# X7A15T-Decoupling.net
KiCad netlist of a schematic drawn in Altium Designer
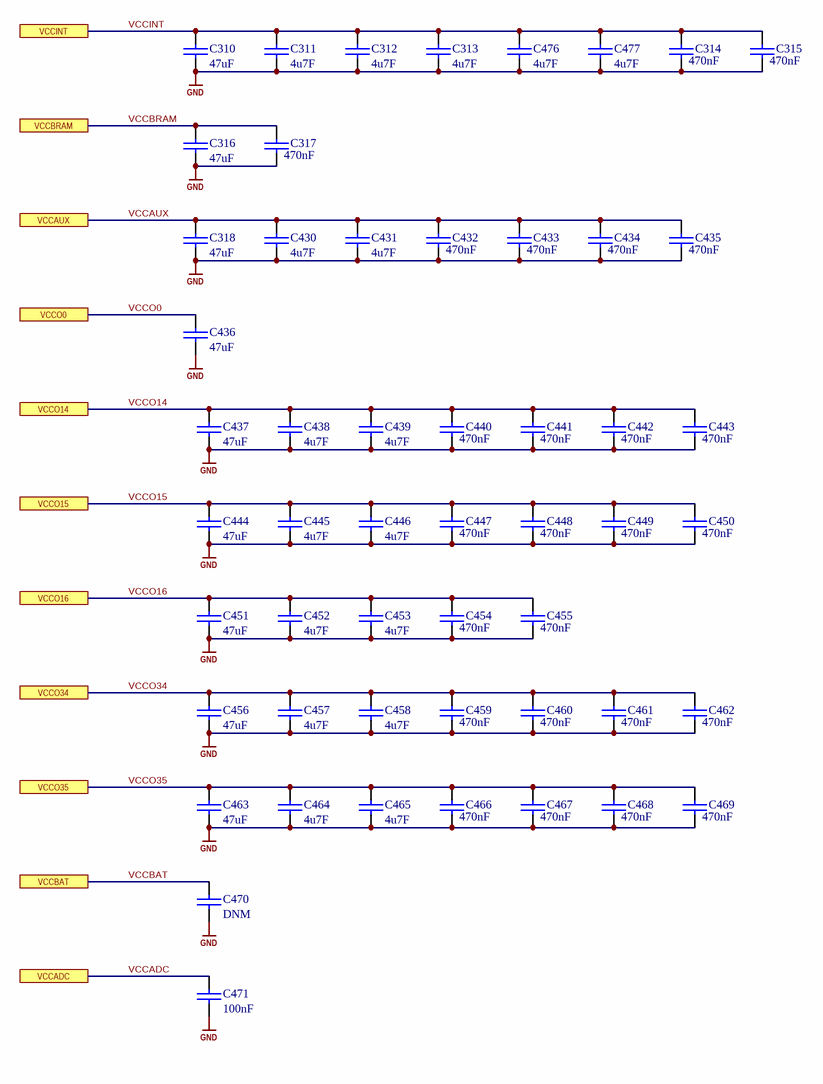
[diagram p0: X7A15T-Decoupling.SchDoc]

(export (version "E")
  (design (tool "Eeschema 10.0.6"))
  (components
    (comp (ref "C310")
      (value "47uF")
      (footprint "C0805 Reflow")
      (description "CAP CER 47UF 10V X5R 0805")
      (fields (field (name "MFR") "MURATA") (field (name "02. DISTRIBUTOR PART NUMBER") "490-9961-6-ND"))
      (libsource (lib "SCT8-Board1") (part "CAP"))
    )
    (comp (ref "C311")
      (value "4u7F")
      (footprint "C0402 Reflow")
      (description "CAP CER 4.7UF 6.3V X5R 0402")
      (fields
        (field (name "02. DISTRIBUTOR PART NUMBER") "1276-1481-6-ND")
        (field (name "07. MANUFACTURER  PART NUMBER") "CL05A475KQ5NRNC")
      )
      (libsource (lib "SCT8-Board1") (part "CAP"))
    )
    (comp (ref "C312")
      (value "4u7F")
      (footprint "C0402 Reflow")
      (description "CAP CER 4.7UF 6.3V X5R 0402")
      (fields
        (field (name "02. DISTRIBUTOR PART NUMBER") "1276-1481-6-ND")
        (field (name "07. MANUFACTURER  PART NUMBER") "CL05A475KQ5NRNC")
      )
      (libsource (lib "SCT8-Board1") (part "CAP"))
    )
    (comp (ref "C313")
      (value "4u7F")
      (footprint "C0402 Reflow")
      (description "CAP CER 4.7UF 6.3V X5R 0402")
      (fields
        (field (name "02. DISTRIBUTOR PART NUMBER") "1276-1481-6-ND")
        (field (name "07. MANUFACTURER  PART NUMBER") "CL05A475KQ5NRNC")
      )
      (libsource (lib "SCT8-Board1") (part "CAP"))
    )
    (comp (ref "C314")
      (value "470nF")
      (footprint "C0402 Reflow")
      (description "CAP CER 0.47UF 10V X5R 0402")
      (fields
        (field (name "02. DISTRIBUTOR PART NUMBER") "1276-1173-6-ND")
        (field (name "07. MANUFACTURER  PART NUMBER") "CL05A474KP5NNNC")
      )
      (libsource (lib "SCT8-Board1") (part "CAP"))
    )
    (comp (ref "C315")
      (value "470nF")
      (footprint "C0402 Reflow")
      (description "CAP CER 0.47UF 10V X5R 0402")
      (fields
        (field (name "02. DISTRIBUTOR PART NUMBER") "1276-1173-6-ND")
        (field (name "07. MANUFACTURER  PART NUMBER") "CL05A474KP5NNNC")
      )
      (libsource (lib "SCT8-Board1") (part "CAP"))
    )
    (comp (ref "C316")
      (value "47uF")
      (footprint "C0805 Reflow")
      (description "CAP CER 47UF 10V X5R 0805")
      (fields (field (name "MFR") "MURATA") (field (name "02. DISTRIBUTOR PART NUMBER") "490-9961-6-ND"))
      (libsource (lib "SCT8-Board1") (part "CAP"))
    )
    (comp (ref "C317")
      (value "470nF")
      (footprint "C0402 Reflow")
      (description "CAP CER 0.47UF 10V X5R 0402")
      (fields
        (field (name "02. DISTRIBUTOR PART NUMBER") "1276-1173-6-ND")
        (field (name "07. MANUFACTURER  PART NUMBER") "CL05A474KP5NNNC")
      )
      (libsource (lib "SCT8-Board1") (part "CAP"))
    )
    (comp (ref "C318")
      (value "47uF")
      (footprint "C0805 Reflow")
      (description "CAP CER 47UF 10V X5R 0805")
      (fields (field (name "MFR") "MURATA") (field (name "02. DISTRIBUTOR PART NUMBER") "490-9961-6-ND"))
      (libsource (lib "SCT8-Board1") (part "CAP"))
    )
    (comp (ref "C430")
      (value "4u7F")
      (footprint "C0402 Reflow")
      (description "CAP CER 4.7UF 6.3V X5R 0402")
      (fields
        (field (name "02. DISTRIBUTOR PART NUMBER") "1276-1481-6-ND")
        (field (name "07. MANUFACTURER  PART NUMBER") "CL05A475KQ5NRNC")
      )
      (libsource (lib "SCT8-Board1") (part "CAP"))
    )
    (comp (ref "C431")
      (value "4u7F")
      (footprint "C0402 Reflow")
      (description "CAP CER 4.7UF 6.3V X5R 0402")
      (fields
        (field (name "02. DISTRIBUTOR PART NUMBER") "1276-1481-6-ND")
        (field (name "07. MANUFACTURER  PART NUMBER") "CL05A475KQ5NRNC")
      )
      (libsource (lib "SCT8-Board1") (part "CAP"))
    )
    (comp (ref "C432")
      (value "470nF")
      (footprint "C0402 Reflow")
      (description "CAP CER 0.47UF 10V X5R 0402")
      (fields
        (field (name "02. DISTRIBUTOR PART NUMBER") "1276-1173-6-ND")
        (field (name "07. MANUFACTURER  PART NUMBER") "CL05A474KP5NNNC")
      )
      (libsource (lib "SCT8-Board1") (part "CAP"))
    )
    (comp (ref "C433")
      (value "470nF")
      (footprint "C0402 Reflow")
      (description "CAP CER 0.47UF 10V X5R 0402")
      (fields
        (field (name "02. DISTRIBUTOR PART NUMBER") "1276-1173-6-ND")
        (field (name "07. MANUFACTURER  PART NUMBER") "CL05A474KP5NNNC")
      )
      (libsource (lib "SCT8-Board1") (part "CAP"))
    )
    (comp (ref "C434")
      (value "470nF")
      (footprint "C0402 Reflow")
      (description "CAP CER 0.47UF 10V X5R 0402")
      (fields
        (field (name "02. DISTRIBUTOR PART NUMBER") "1276-1173-6-ND")
        (field (name "07. MANUFACTURER  PART NUMBER") "CL05A474KP5NNNC")
      )
      (libsource (lib "SCT8-Board1") (part "CAP"))
    )
    (comp (ref "C435")
      (value "470nF")
      (footprint "C0402 Reflow")
      (description "CAP CER 0.47UF 10V X5R 0402")
      (fields
        (field (name "02. DISTRIBUTOR PART NUMBER") "1276-1173-6-ND")
        (field (name "07. MANUFACTURER  PART NUMBER") "CL05A474KP5NNNC")
      )
      (libsource (lib "SCT8-Board1") (part "CAP"))
    )
    (comp (ref "C436")
      (value "47uF")
      (footprint "C0805 Reflow")
      (description "CAP CER 47UF 10V X5R 0805")
      (fields (field (name "MFR") "MURATA") (field (name "02. DISTRIBUTOR PART NUMBER") "490-9961-6-ND"))
      (libsource (lib "SCT8-Board1") (part "CAP"))
    )
    (comp (ref "C437")
      (value "47uF")
      (footprint "C0805 Reflow")
      (description "CAP CER 47UF 10V X5R 0805")
      (fields (field (name "MFR") "MURATA") (field (name "02. DISTRIBUTOR PART NUMBER") "490-9961-6-ND"))
      (libsource (lib "SCT8-Board1") (part "CAP"))
    )
    (comp (ref "C438")
      (value "4u7F")
      (footprint "C0402 Reflow")
      (description "CAP CER 4.7UF 6.3V X5R 0402")
      (fields
        (field (name "02. DISTRIBUTOR PART NUMBER") "1276-1481-6-ND")
        (field (name "07. MANUFACTURER  PART NUMBER") "CL05A475KQ5NRNC")
      )
      (libsource (lib "SCT8-Board1") (part "CAP"))
    )
    (comp (ref "C439")
      (value "4u7F")
      (footprint "C0402 Reflow")
      (description "CAP CER 4.7UF 6.3V X5R 0402")
      (fields
        (field (name "02. DISTRIBUTOR PART NUMBER") "1276-1481-6-ND")
        (field (name "07. MANUFACTURER  PART NUMBER") "CL05A475KQ5NRNC")
      )
      (libsource (lib "SCT8-Board1") (part "CAP"))
    )
    (comp (ref "C440")
      (value "470nF")
      (footprint "C0402 Reflow")
      (description "CAP CER 0.47UF 10V X5R 0402")
      (fields
        (field (name "02. DISTRIBUTOR PART NUMBER") "1276-1173-6-ND")
        (field (name "07. MANUFACTURER  PART NUMBER") "CL05A474KP5NNNC")
      )
      (libsource (lib "SCT8-Board1") (part "CAP"))
    )
    (comp (ref "C441")
      (value "470nF")
      (footprint "C0402 Reflow")
      (description "CAP CER 0.47UF 10V X5R 0402")
      (fields
        (field (name "02. DISTRIBUTOR PART NUMBER") "1276-1173-6-ND")
        (field (name "07. MANUFACTURER  PART NUMBER") "CL05A474KP5NNNC")
      )
      (libsource (lib "SCT8-Board1") (part "CAP"))
    )
    (comp (ref "C442")
      (value "470nF")
      (footprint "C0402 Reflow")
      (description "CAP CER 0.47UF 10V X5R 0402")
      (fields
        (field (name "02. DISTRIBUTOR PART NUMBER") "1276-1173-6-ND")
        (field (name "07. MANUFACTURER  PART NUMBER") "CL05A474KP5NNNC")
      )
      (libsource (lib "SCT8-Board1") (part "CAP"))
    )
    (comp (ref "C443")
      (value "470nF")
      (footprint "C0402 Reflow")
      (description "CAP CER 0.47UF 10V X5R 0402")
      (fields
        (field (name "02. DISTRIBUTOR PART NUMBER") "1276-1173-6-ND")
        (field (name "07. MANUFACTURER  PART NUMBER") "CL05A474KP5NNNC")
      )
      (libsource (lib "SCT8-Board1") (part "CAP"))
    )
    (comp (ref "C444")
      (value "47uF")
      (footprint "C0805 Reflow")
      (description "CAP CER 47UF 10V X5R 0805")
      (fields (field (name "MFR") "MURATA") (field (name "02. DISTRIBUTOR PART NUMBER") "490-9961-6-ND"))
      (libsource (lib "SCT8-Board1") (part "CAP"))
    )
    (comp (ref "C445")
      (value "4u7F")
      (footprint "C0402 Reflow")
      (description "CAP CER 4.7UF 6.3V X5R 0402")
      (fields
        (field (name "02. DISTRIBUTOR PART NUMBER") "1276-1481-6-ND")
        (field (name "07. MANUFACTURER  PART NUMBER") "CL05A475KQ5NRNC")
      )
      (libsource (lib "SCT8-Board1") (part "CAP"))
    )
    (comp (ref "C446")
      (value "4u7F")
      (footprint "C0402 Reflow")
      (description "CAP CER 4.7UF 6.3V X5R 0402")
      (fields
        (field (name "02. DISTRIBUTOR PART NUMBER") "1276-1481-6-ND")
        (field (name "07. MANUFACTURER  PART NUMBER") "CL05A475KQ5NRNC")
      )
      (libsource (lib "SCT8-Board1") (part "CAP"))
    )
    (comp (ref "C447")
      (value "470nF")
      (footprint "C0402 Reflow")
      (description "CAP CER 0.47UF 10V X5R 0402")
      (fields
        (field (name "02. DISTRIBUTOR PART NUMBER") "1276-1173-6-ND")
        (field (name "07. MANUFACTURER  PART NUMBER") "CL05A474KP5NNNC")
      )
      (libsource (lib "SCT8-Board1") (part "CAP"))
    )
    (comp (ref "C448")
      (value "470nF")
      (footprint "C0402 Reflow")
      (description "CAP CER 0.47UF 10V X5R 0402")
      (fields
        (field (name "02. DISTRIBUTOR PART NUMBER") "1276-1173-6-ND")
        (field (name "07. MANUFACTURER  PART NUMBER") "CL05A474KP5NNNC")
      )
      (libsource (lib "SCT8-Board1") (part "CAP"))
    )
    (comp (ref "C449")
      (value "470nF")
      (footprint "C0402 Reflow")
      (description "CAP CER 0.47UF 10V X5R 0402")
      (fields
        (field (name "02. DISTRIBUTOR PART NUMBER") "1276-1173-6-ND")
        (field (name "07. MANUFACTURER  PART NUMBER") "CL05A474KP5NNNC")
      )
      (libsource (lib "SCT8-Board1") (part "CAP"))
    )
    (comp (ref "C450")
      (value "470nF")
      (footprint "C0402 Reflow")
      (description "CAP CER 0.47UF 10V X5R 0402")
      (fields
        (field (name "02. DISTRIBUTOR PART NUMBER") "1276-1173-6-ND")
        (field (name "07. MANUFACTURER  PART NUMBER") "CL05A474KP5NNNC")
      )
      (libsource (lib "SCT8-Board1") (part "CAP"))
    )
    (comp (ref "C451")
      (value "47uF")
      (footprint "C0805 Reflow")
      (description "CAP CER 47UF 10V X5R 0805")
      (fields (field (name "MFR") "MURATA") (field (name "02. DISTRIBUTOR PART NUMBER") "490-9961-6-ND"))
      (libsource (lib "SCT8-Board1") (part "CAP"))
    )
    (comp (ref "C452")
      (value "4u7F")
      (footprint "C0402 Reflow")
      (description "CAP CER 4.7UF 6.3V X5R 0402")
      (fields
        (field (name "02. DISTRIBUTOR PART NUMBER") "1276-1481-6-ND")
        (field (name "07. MANUFACTURER  PART NUMBER") "CL05A475KQ5NRNC")
      )
      (libsource (lib "SCT8-Board1") (part "CAP"))
    )
    (comp (ref "C453")
      (value "4u7F")
      (footprint "C0402 Reflow")
      (description "CAP CER 4.7UF 6.3V X5R 0402")
      (fields
        (field (name "02. DISTRIBUTOR PART NUMBER") "1276-1481-6-ND")
        (field (name "07. MANUFACTURER  PART NUMBER") "CL05A475KQ5NRNC")
      )
      (libsource (lib "SCT8-Board1") (part "CAP"))
    )
    (comp (ref "C454")
      (value "470nF")
      (footprint "C0402 Reflow")
      (description "CAP CER 0.47UF 10V X5R 0402")
      (fields
        (field (name "02. DISTRIBUTOR PART NUMBER") "1276-1173-6-ND")
        (field (name "07. MANUFACTURER  PART NUMBER") "CL05A474KP5NNNC")
      )
      (libsource (lib "SCT8-Board1") (part "CAP"))
    )
    (comp (ref "C455")
      (value "470nF")
      (footprint "C0402 Reflow")
      (description "CAP CER 0.47UF 10V X5R 0402")
      (fields
        (field (name "02. DISTRIBUTOR PART NUMBER") "1276-1173-6-ND")
        (field (name "07. MANUFACTURER  PART NUMBER") "CL05A474KP5NNNC")
      )
      (libsource (lib "SCT8-Board1") (part "CAP"))
    )
    (comp (ref "C456")
      (value "47uF")
      (footprint "C0805 Reflow")
      (description "CAP CER 47UF 10V X5R 0805")
      (fields (field (name "MFR") "MURATA") (field (name "02. DISTRIBUTOR PART NUMBER") "490-9961-6-ND"))
      (libsource (lib "SCT8-Board1") (part "CAP"))
    )
    (comp (ref "C457")
      (value "4u7F")
      (footprint "C0402 Reflow")
      (description "CAP CER 4.7UF 6.3V X5R 0402")
      (fields
        (field (name "02. DISTRIBUTOR PART NUMBER") "1276-1481-6-ND")
        (field (name "07. MANUFACTURER  PART NUMBER") "CL05A475KQ5NRNC")
      )
      (libsource (lib "SCT8-Board1") (part "CAP"))
    )
    (comp (ref "C458")
      (value "4u7F")
      (footprint "C0402 Reflow")
      (description "CAP CER 4.7UF 6.3V X5R 0402")
      (fields
        (field (name "02. DISTRIBUTOR PART NUMBER") "1276-1481-6-ND")
        (field (name "07. MANUFACTURER  PART NUMBER") "CL05A475KQ5NRNC")
      )
      (libsource (lib "SCT8-Board1") (part "CAP"))
    )
    (comp (ref "C459")
      (value "470nF")
      (footprint "C0402 Reflow")
      (description "CAP CER 0.47UF 10V X5R 0402")
      (fields
        (field (name "02. DISTRIBUTOR PART NUMBER") "1276-1173-6-ND")
        (field (name "07. MANUFACTURER  PART NUMBER") "CL05A474KP5NNNC")
      )
      (libsource (lib "SCT8-Board1") (part "CAP"))
    )
    (comp (ref "C460")
      (value "470nF")
      (footprint "C0402 Reflow")
      (description "CAP CER 0.47UF 10V X5R 0402")
      (fields
        (field (name "02. DISTRIBUTOR PART NUMBER") "1276-1173-6-ND")
        (field (name "07. MANUFACTURER  PART NUMBER") "CL05A474KP5NNNC")
      )
      (libsource (lib "SCT8-Board1") (part "CAP"))
    )
    (comp (ref "C461")
      (value "470nF")
      (footprint "C0402 Reflow")
      (description "CAP CER 0.47UF 10V X5R 0402")
      (fields
        (field (name "02. DISTRIBUTOR PART NUMBER") "1276-1173-6-ND")
        (field (name "07. MANUFACTURER  PART NUMBER") "CL05A474KP5NNNC")
      )
      (libsource (lib "SCT8-Board1") (part "CAP"))
    )
    (comp (ref "C462")
      (value "470nF")
      (footprint "C0402 Reflow")
      (description "CAP CER 0.47UF 10V X5R 0402")
      (fields
        (field (name "02. DISTRIBUTOR PART NUMBER") "1276-1173-6-ND")
        (field (name "07. MANUFACTURER  PART NUMBER") "CL05A474KP5NNNC")
      )
      (libsource (lib "SCT8-Board1") (part "CAP"))
    )
    (comp (ref "C463")
      (value "47uF")
      (footprint "C0805 Reflow")
      (description "CAP CER 47UF 10V X5R 0805")
      (fields (field (name "MFR") "MURATA") (field (name "02. DISTRIBUTOR PART NUMBER") "490-9961-6-ND"))
      (libsource (lib "SCT8-Board1") (part "CAP"))
    )
    (comp (ref "C464")
      (value "4u7F")
      (footprint "C0402 Reflow")
      (description "CAP CER 4.7UF 6.3V X5R 0402")
      (fields
        (field (name "02. DISTRIBUTOR PART NUMBER") "1276-1481-6-ND")
        (field (name "07. MANUFACTURER  PART NUMBER") "CL05A475KQ5NRNC")
      )
      (libsource (lib "SCT8-Board1") (part "CAP"))
    )
    (comp (ref "C465")
      (value "4u7F")
      (footprint "C0402 Reflow")
      (description "CAP CER 4.7UF 6.3V X5R 0402")
      (fields
        (field (name "02. DISTRIBUTOR PART NUMBER") "1276-1481-6-ND")
        (field (name "07. MANUFACTURER  PART NUMBER") "CL05A475KQ5NRNC")
      )
      (libsource (lib "SCT8-Board1") (part "CAP"))
    )
    (comp (ref "C466")
      (value "470nF")
      (footprint "C0402 Reflow")
      (description "CAP CER 0.47UF 10V X5R 0402")
      (fields
        (field (name "02. DISTRIBUTOR PART NUMBER") "1276-1173-6-ND")
        (field (name "07. MANUFACTURER  PART NUMBER") "CL05A474KP5NNNC")
      )
      (libsource (lib "SCT8-Board1") (part "CAP"))
    )
    (comp (ref "C467")
      (value "470nF")
      (footprint "C0402 Reflow")
      (description "CAP CER 0.47UF 10V X5R 0402")
      (fields
        (field (name "02. DISTRIBUTOR PART NUMBER") "1276-1173-6-ND")
        (field (name "07. MANUFACTURER  PART NUMBER") "CL05A474KP5NNNC")
      )
      (libsource (lib "SCT8-Board1") (part "CAP"))
    )
    (comp (ref "C468")
      (value "470nF")
      (footprint "C0402 Reflow")
      (description "CAP CER 0.47UF 10V X5R 0402")
      (fields
        (field (name "02. DISTRIBUTOR PART NUMBER") "1276-1173-6-ND")
        (field (name "07. MANUFACTURER  PART NUMBER") "CL05A474KP5NNNC")
      )
      (libsource (lib "SCT8-Board1") (part "CAP"))
    )
    (comp (ref "C469")
      (value "470nF")
      (footprint "C0402 Reflow")
      (description "CAP CER 0.47UF 10V X5R 0402")
      (fields
        (field (name "02. DISTRIBUTOR PART NUMBER") "1276-1173-6-ND")
        (field (name "07. MANUFACTURER  PART NUMBER") "CL05A474KP5NNNC")
      )
      (libsource (lib "SCT8-Board1") (part "CAP"))
    )
    (comp (ref "C470")
      (value "DNM")
      (footprint "C0402 Reflow")
      (description "CAP CER 4.7UF 6.3V X5R 0402")
      (fields
        (field (name "02. DISTRIBUTOR PART NUMBER") "1276-1481-6-ND")
        (field (name "07. MANUFACTURER  PART NUMBER") "CL05A475KQ5NRNC")
      )
      (libsource (lib "SCT8-Board1") (part "CAP"))
    )
    (comp (ref "C471")
      (value "100nF")
      (footprint "C0402 Reflow")
      (description "CAP CER 0.1UF 25V X7R 0402")
      (fields
        (field (name "02. DISTRIBUTOR PART NUMBER") "311-2077-6-ND")
        (field (name "07. MANUFACTURER  PART NUMBER") "CC0402KRX7R8BB104")
      )
      (libsource (lib "SCT8-Board1") (part "CAP"))
    )
    (comp (ref "C476")
      (value "4u7F")
      (footprint "C0402 Reflow")
      (description "CAP CER 4.7UF 6.3V X5R 0402")
      (fields
        (field (name "02. DISTRIBUTOR PART NUMBER") "1276-1481-6-ND")
        (field (name "07. MANUFACTURER  PART NUMBER") "CL05A475KQ5NRNC")
      )
      (libsource (lib "SCT8-Board1") (part "CAP"))
    )
    (comp (ref "C477")
      (value "4u7F")
      (footprint "C0402 Reflow")
      (description "CAP CER 4.7UF 6.3V X5R 0402")
      (fields
        (field (name "02. DISTRIBUTOR PART NUMBER") "1276-1481-6-ND")
        (field (name "07. MANUFACTURER  PART NUMBER") "CL05A475KQ5NRNC")
      )
      (libsource (lib "SCT8-Board1") (part "CAP"))
    )
  )
  (nets
    (net (code "1") (name "/VCCADC") (class "Default")
      (node (ref "C471") (pin "1") (pinfunction "1_1") (pintype "passive"))
    )
    (net (code "2") (name "/VCCAUX") (class "Default")
      (node (ref "C318") (pin "1") (pinfunction "1_1") (pintype "passive"))
      (node (ref "C430") (pin "1") (pinfunction "1_1") (pintype "passive"))
      (node (ref "C431") (pin "1") (pinfunction "1_1") (pintype "passive"))
      (node (ref "C432") (pin "1") (pinfunction "1_1") (pintype "passive"))
      (node (ref "C433") (pin "1") (pinfunction "1_1") (pintype "passive"))
      (node (ref "C434") (pin "1") (pinfunction "1_1") (pintype "passive"))
      (node (ref "C435") (pin "1") (pinfunction "1_1") (pintype "passive"))
    )
    (net (code "3") (name "/VCCBAT") (class "Default")
      (node (ref "C470") (pin "1") (pinfunction "1_1") (pintype "passive"))
    )
    (net (code "4") (name "/VCCBRAM") (class "Default")
      (node (ref "C316") (pin "1") (pinfunction "1_1") (pintype "passive"))
      (node (ref "C317") (pin "1") (pinfunction "1_1") (pintype "passive"))
    )
    (net (code "5") (name "/VCCINT") (class "Default")
      (node (ref "C310") (pin "1") (pinfunction "1_1") (pintype "passive"))
      (node (ref "C311") (pin "1") (pinfunction "1_1") (pintype "passive"))
      (node (ref "C312") (pin "1") (pinfunction "1_1") (pintype "passive"))
      (node (ref "C313") (pin "1") (pinfunction "1_1") (pintype "passive"))
      (node (ref "C314") (pin "1") (pinfunction "1_1") (pintype "passive"))
      (node (ref "C315") (pin "1") (pinfunction "1_1") (pintype "passive"))
      (node (ref "C476") (pin "1") (pinfunction "1_1") (pintype "passive"))
      (node (ref "C477") (pin "1") (pinfunction "1_1") (pintype "passive"))
    )
    (net (code "6") (name "/VCCO0") (class "Default")
      (node (ref "C436") (pin "1") (pinfunction "1_1") (pintype "passive"))
    )
    (net (code "7") (name "/VCCO14") (class "Default")
      (node (ref "C437") (pin "1") (pinfunction "1_1") (pintype "passive"))
      (node (ref "C438") (pin "1") (pinfunction "1_1") (pintype "passive"))
      (node (ref "C439") (pin "1") (pinfunction "1_1") (pintype "passive"))
      (node (ref "C440") (pin "1") (pinfunction "1_1") (pintype "passive"))
      (node (ref "C441") (pin "1") (pinfunction "1_1") (pintype "passive"))
      (node (ref "C442") (pin "1") (pinfunction "1_1") (pintype "passive"))
      (node (ref "C443") (pin "1") (pinfunction "1_1") (pintype "passive"))
    )
    (net (code "8") (name "/VCCO15") (class "Default")
      (node (ref "C444") (pin "1") (pinfunction "1_1") (pintype "passive"))
      (node (ref "C445") (pin "1") (pinfunction "1_1") (pintype "passive"))
      (node (ref "C446") (pin "1") (pinfunction "1_1") (pintype "passive"))
      (node (ref "C447") (pin "1") (pinfunction "1_1") (pintype "passive"))
      (node (ref "C448") (pin "1") (pinfunction "1_1") (pintype "passive"))
      (node (ref "C449") (pin "1") (pinfunction "1_1") (pintype "passive"))
      (node (ref "C450") (pin "1") (pinfunction "1_1") (pintype "passive"))
    )
    (net (code "9") (name "/VCCO16") (class "Default")
      (node (ref "C451") (pin "1") (pinfunction "1_1") (pintype "passive"))
      (node (ref "C452") (pin "1") (pinfunction "1_1") (pintype "passive"))
      (node (ref "C453") (pin "1") (pinfunction "1_1") (pintype "passive"))
      (node (ref "C454") (pin "1") (pinfunction "1_1") (pintype "passive"))
      (node (ref "C455") (pin "1") (pinfunction "1_1") (pintype "passive"))
    )
    (net (code "10") (name "/VCCO34") (class "Default")
      (node (ref "C456") (pin "1") (pinfunction "1_1") (pintype "passive"))
      (node (ref "C457") (pin "1") (pinfunction "1_1") (pintype "passive"))
      (node (ref "C458") (pin "1") (pinfunction "1_1") (pintype "passive"))
      (node (ref "C459") (pin "1") (pinfunction "1_1") (pintype "passive"))
      (node (ref "C460") (pin "1") (pinfunction "1_1") (pintype "passive"))
      (node (ref "C461") (pin "1") (pinfunction "1_1") (pintype "passive"))
      (node (ref "C462") (pin "1") (pinfunction "1_1") (pintype "passive"))
    )
    (net (code "11") (name "/VCCO35") (class "Default")
      (node (ref "C463") (pin "1") (pinfunction "1_1") (pintype "passive"))
      (node (ref "C464") (pin "1") (pinfunction "1_1") (pintype "passive"))
      (node (ref "C465") (pin "1") (pinfunction "1_1") (pintype "passive"))
      (node (ref "C466") (pin "1") (pinfunction "1_1") (pintype "passive"))
      (node (ref "C467") (pin "1") (pinfunction "1_1") (pintype "passive"))
      (node (ref "C468") (pin "1") (pinfunction "1_1") (pintype "passive"))
      (node (ref "C469") (pin "1") (pinfunction "1_1") (pintype "passive"))
    )
    (net (code "12") (name "GND") (class "Default")
      (node (ref "C310") (pin "2") (pinfunction "2_2") (pintype "passive"))
      (node (ref "C311") (pin "2") (pinfunction "2_2") (pintype "passive"))
      (node (ref "C312") (pin "2") (pinfunction "2_2") (pintype "passive"))
      (node (ref "C313") (pin "2") (pinfunction "2_2") (pintype "passive"))
      (node (ref "C314") (pin "2") (pinfunction "2_2") (pintype "passive"))
      (node (ref "C315") (pin "2") (pinfunction "2_2") (pintype "passive"))
      (node (ref "C316") (pin "2") (pinfunction "2_2") (pintype "passive"))
      (node (ref "C317") (pin "2") (pinfunction "2_2") (pintype "passive"))
      (node (ref "C318") (pin "2") (pinfunction "2_2") (pintype "passive"))
      (node (ref "C430") (pin "2") (pinfunction "2_2") (pintype "passive"))
      (node (ref "C431") (pin "2") (pinfunction "2_2") (pintype "passive"))
      (node (ref "C432") (pin "2") (pinfunction "2_2") (pintype "passive"))
      (node (ref "C433") (pin "2") (pinfunction "2_2") (pintype "passive"))
      (node (ref "C434") (pin "2") (pinfunction "2_2") (pintype "passive"))
      (node (ref "C435") (pin "2") (pinfunction "2_2") (pintype "passive"))
      (node (ref "C436") (pin "2") (pinfunction "2_2") (pintype "passive"))
      (node (ref "C437") (pin "2") (pinfunction "2_2") (pintype "passive"))
      (node (ref "C438") (pin "2") (pinfunction "2_2") (pintype "passive"))
      (node (ref "C439") (pin "2") (pinfunction "2_2") (pintype "passive"))
      (node (ref "C440") (pin "2") (pinfunction "2_2") (pintype "passive"))
      (node (ref "C441") (pin "2") (pinfunction "2_2") (pintype "passive"))
      (node (ref "C442") (pin "2") (pinfunction "2_2") (pintype "passive"))
      (node (ref "C443") (pin "2") (pinfunction "2_2") (pintype "passive"))
      (node (ref "C444") (pin "2") (pinfunction "2_2") (pintype "passive"))
      (node (ref "C445") (pin "2") (pinfunction "2_2") (pintype "passive"))
      (node (ref "C446") (pin "2") (pinfunction "2_2") (pintype "passive"))
      (node (ref "C447") (pin "2") (pinfunction "2_2") (pintype "passive"))
      (node (ref "C448") (pin "2") (pinfunction "2_2") (pintype "passive"))
      (node (ref "C449") (pin "2") (pinfunction "2_2") (pintype "passive"))
      (node (ref "C450") (pin "2") (pinfunction "2_2") (pintype "passive"))
      (node (ref "C451") (pin "2") (pinfunction "2_2") (pintype "passive"))
      (node (ref "C452") (pin "2") (pinfunction "2_2") (pintype "passive"))
      (node (ref "C453") (pin "2") (pinfunction "2_2") (pintype "passive"))
      (node (ref "C454") (pin "2") (pinfunction "2_2") (pintype "passive"))
      (node (ref "C455") (pin "2") (pinfunction "2_2") (pintype "passive"))
      (node (ref "C456") (pin "2") (pinfunction "2_2") (pintype "passive"))
      (node (ref "C457") (pin "2") (pinfunction "2_2") (pintype "passive"))
      (node (ref "C458") (pin "2") (pinfunction "2_2") (pintype "passive"))
      (node (ref "C459") (pin "2") (pinfunction "2_2") (pintype "passive"))
      (node (ref "C460") (pin "2") (pinfunction "2_2") (pintype "passive"))
      (node (ref "C461") (pin "2") (pinfunction "2_2") (pintype "passive"))
      (node (ref "C462") (pin "2") (pinfunction "2_2") (pintype "passive"))
      (node (ref "C463") (pin "2") (pinfunction "2_2") (pintype "passive"))
      (node (ref "C464") (pin "2") (pinfunction "2_2") (pintype "passive"))
      (node (ref "C465") (pin "2") (pinfunction "2_2") (pintype "passive"))
      (node (ref "C466") (pin "2") (pinfunction "2_2") (pintype "passive"))
      (node (ref "C467") (pin "2") (pinfunction "2_2") (pintype "passive"))
      (node (ref "C468") (pin "2") (pinfunction "2_2") (pintype "passive"))
      (node (ref "C469") (pin "2") (pinfunction "2_2") (pintype "passive"))
      (node (ref "C470") (pin "2") (pinfunction "2_2") (pintype "passive"))
      (node (ref "C471") (pin "2") (pinfunction "2_2") (pintype "passive"))
      (node (ref "C476") (pin "2") (pinfunction "2_2") (pintype "passive"))
      (node (ref "C477") (pin "2") (pinfunction "2_2") (pintype "passive"))
    )
  )
)
